# STM32F407VGT6.net
KiCad netlist of a schematic drawn in Altium Designer
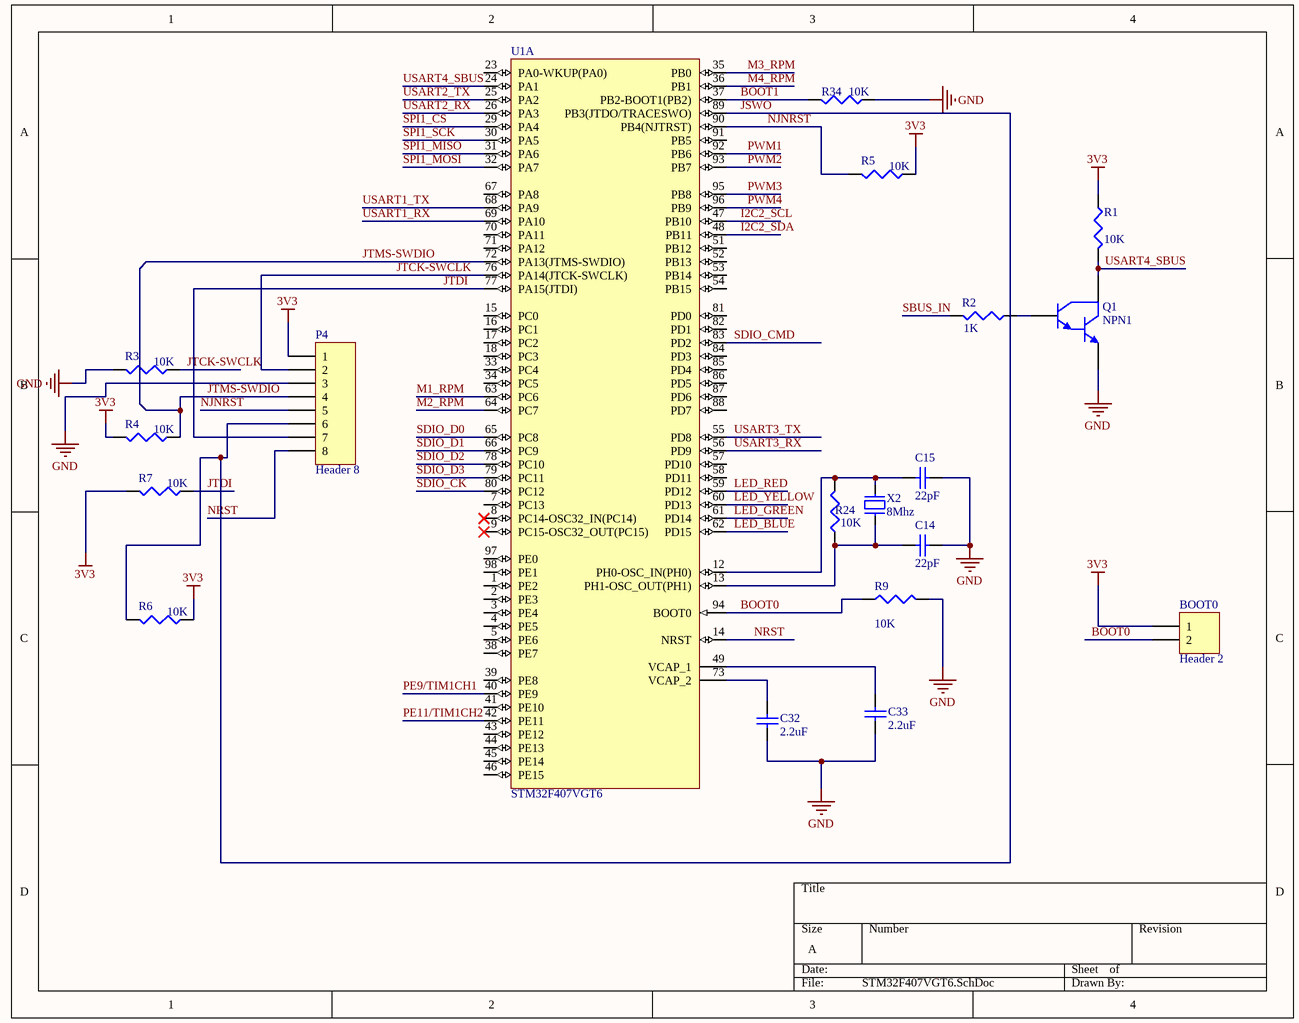
[diagram p0: STM32F407VGT6.SchDoc]

(export (version "E")
  (design (tool "Eeschema 10.0.6"))
  (components
    (comp (ref "BOOT0")
      (value "Header 2")
      (footprint "HDR1X2")
      (description "Header, 2-Pin")
      (fields (field (name "PUBLISHER") "Altium Limited"))
      (libsource (lib "Miscellaneous Connectors") (part "Header 2"))
    )
    (comp (ref "C14")
      (value "22pF")
      (footprint "stm_copter:CAPC1608X95N")
      (description "Capacitor (Semiconductor SIM Model)")
      (fields (field (name "PUBLISHER") "Altium Limited"))
      (libsource (lib "syhaunguyen") (part "Cap Semi"))
    )
    (comp (ref "C15")
      (value "22pF")
      (footprint "stm_copter:CAPC1608X95N")
      (description "Capacitor (Semiconductor SIM Model)")
      (fields (field (name "PUBLISHER") "Altium Limited"))
      (libsource (lib "syhaunguyen") (part "Cap Semi"))
    )
    (comp (ref "C32")
      (value "2.2uF")
      (footprint "stm_copter:CAPC3216X125N")
      (description "Capacitor (Semiconductor SIM Model)")
      (fields (field (name "PUBLISHER") "Altium Limited"))
      (libsource (lib "syhaunguyen") (part "Cap Semi"))
    )
    (comp (ref "C33")
      (value "2.2uF")
      (footprint "stm_copter:CAPC3216X125N")
      (description "Capacitor (Semiconductor SIM Model)")
      (fields (field (name "PUBLISHER") "Altium Limited"))
      (libsource (lib "syhaunguyen") (part "Cap Semi"))
    )
    (comp (ref "P4")
      (value "Header 8")
      (footprint "HDR1X8")
      (description "Header, 8-Pin")
      (fields (field (name "PUBLISHER") "Altium Limited"))
      (libsource (lib "Miscellaneous Connectors") (part "Header 8"))
    )
    (comp (ref "Q1")
      (value "NPN1")
      (footprint "TO-92")
      (description "NPN Darlington Bipolar Transistor")
      (fields (field (name "PUBLISHER") "Altium Limited"))
      (libsource (lib "Miscellaneous Devices") (part "NPN1"))
    )
    (comp (ref "R1")
      (value "10K")
      (footprint "stm_copter:RESC2012X60N")
      (description "Resistor")
      (fields (field (name "PUBLISHER") "Altium Limited"))
      (libsource (lib "Miscellaneous Devices") (part "Res3"))
    )
    (comp (ref "R2")
      (value "1K")
      (footprint "stm_copter:RESC2012X60N")
      (description "Resistor")
      (fields (field (name "PUBLISHER") "Altium Limited"))
      (libsource (lib "Miscellaneous Devices") (part "Res3"))
    )
    (comp (ref "R3")
      (value "10K")
      (footprint "stm_copter:RESC2012X60N")
      (description "Resistor")
      (fields (field (name "PUBLISHER") "Altium Limited"))
      (libsource (lib "Miscellaneous Devices") (part "Res3"))
    )
    (comp (ref "R4")
      (value "10K")
      (footprint "stm_copter:RESC2012X60N")
      (description "Resistor")
      (fields (field (name "PUBLISHER") "Altium Limited"))
      (libsource (lib "Miscellaneous Devices") (part "Res3"))
    )
    (comp (ref "R5")
      (value "10K")
      (footprint "stm_copter:RESC2012X60N")
      (description "Resistor")
      (fields (field (name "PUBLISHER") "Altium Limited"))
      (libsource (lib "Miscellaneous Devices") (part "Res3"))
    )
    (comp (ref "R6")
      (value "10K")
      (footprint "stm_copter:RESC2012X60N")
      (description "Resistor")
      (fields (field (name "PUBLISHER") "Altium Limited"))
      (libsource (lib "Miscellaneous Devices") (part "Res3"))
    )
    (comp (ref "R7")
      (value "10K")
      (footprint "stm_copter:RESC2012X60N")
      (description "Resistor")
      (fields (field (name "PUBLISHER") "Altium Limited"))
      (libsource (lib "Miscellaneous Devices") (part "Res3"))
    )
    (comp (ref "R9")
      (value "10K")
      (footprint "stm_copter:RESC2012X60N")
      (description "Resistor")
      (fields (field (name "PUBLISHER") "Altium Limited"))
      (libsource (lib "Miscellaneous Devices") (part "Res3"))
    )
    (comp (ref "R24")
      (value "10K")
      (footprint "stm_copter:RESC2012X60N")
      (description "Resistor")
      (fields (field (name "PUBLISHER") "Altium Limited"))
      (libsource (lib "Miscellaneous Devices") (part "Res3"))
    )
    (comp (ref "R34")
      (value "10K")
      (footprint "stm_copter:RESC2012X60N")
      (description "Resistor")
      (fields (field (name "PUBLISHER") "Altium Limited"))
      (libsource (lib "Miscellaneous Devices") (part "Res3"))
    )
    (comp (ref "U1")
      (value "STM32F407VGT6")
      (footprint "STM-LQFP100_N")
      (fields (field (name "MANUFACTURER") "STMicroelectronics"))
      (libsource (lib "STMicroelectronics STM32 F4") (part "STM32F407VGT6"))
    )
    (comp (ref "X2")
      (value "8Mhz")
      (footprint "XT2")
      (description "Crystal For all Crystal 2pin.")
      (libsource (lib "syhaunguyen") (part "XT2"))
    )
  )
  (nets
    (net (code "1") (name "/BOOT0") (class "Default")
      (node (ref "BOOT0") (pin "2") (pinfunction "2_2") (pintype "passive"))
      (node (ref "R9") (pin "1") (pinfunction "1_1") (pintype "passive"))
      (node (ref "U1") (pin "94") (pinfunction "BOOT0_94") (pintype "input"))
    )
    (net (code "2") (name "/BOOT1") (class "Default")
      (node (ref "R34") (pin "2") (pinfunction "2_2") (pintype "passive"))
      (node (ref "U1") (pin "37") (pinfunction "PB2-BOOT1(PB2)_37") (pintype "bidirectional"))
    )
    (net (code "3") (name "/I2C2_SCL") (class "Default")
      (node (ref "U1") (pin "47") (pinfunction "PB10_47") (pintype "bidirectional"))
    )
    (net (code "4") (name "/I2C2_SDA") (class "Default")
      (node (ref "U1") (pin "48") (pinfunction "PB11_48") (pintype "bidirectional"))
    )
    (net (code "5") (name "/JSWO") (class "Default")
      (node (ref "P4") (pin "6") (pinfunction "6_6") (pintype "passive"))
      (node (ref "R6") (pin "2") (pinfunction "2_2") (pintype "passive"))
      (node (ref "U1") (pin "89") (pinfunction "PB3(JTDO/TRACESWO)_89") (pintype "bidirectional"))
    )
    (net (code "6") (name "/JTCK-SWCLK") (class "Default")
      (node (ref "P4") (pin "2") (pinfunction "2_2") (pintype "passive"))
      (node (ref "R3") (pin "1") (pinfunction "1_1") (pintype "passive"))
      (node (ref "U1") (pin "76") (pinfunction "PA14(JTCK-SWCLK)_76") (pintype "bidirectional"))
    )
    (net (code "7") (name "/JTDI") (class "Default")
      (node (ref "P4") (pin "7") (pinfunction "7_7") (pintype "passive"))
      (node (ref "R7") (pin "1") (pinfunction "1_1") (pintype "passive"))
      (node (ref "U1") (pin "77") (pinfunction "PA15(JTDI)_77") (pintype "bidirectional"))
    )
    (net (code "8") (name "/JTMS-SWDIO") (class "Default")
      (node (ref "P4") (pin "4") (pinfunction "4_4") (pintype "passive"))
      (node (ref "R4") (pin "1") (pinfunction "1_1") (pintype "passive"))
      (node (ref "U1") (pin "72") (pinfunction "PA13(JTMS-SWDIO)_72") (pintype "bidirectional"))
    )
    (net (code "9") (name "/LED_BLUE") (class "Default")
      (node (ref "U1") (pin "62") (pinfunction "PD15_62") (pintype "bidirectional"))
    )
    (net (code "10") (name "/LED_GREEN") (class "Default")
      (node (ref "U1") (pin "61") (pinfunction "PD14_61") (pintype "bidirectional"))
    )
    (net (code "11") (name "/LED_RED") (class "Default")
      (node (ref "U1") (pin "59") (pinfunction "PD12_59") (pintype "bidirectional"))
    )
    (net (code "12") (name "/LED_YELLOW") (class "Default")
      (node (ref "U1") (pin "60") (pinfunction "PD13_60") (pintype "bidirectional"))
    )
    (net (code "13") (name "/M1_RPM") (class "Default")
      (node (ref "U1") (pin "63") (pinfunction "PC6_63") (pintype "bidirectional"))
    )
    (net (code "14") (name "/M2_RPM") (class "Default")
      (node (ref "U1") (pin "64") (pinfunction "PC7_64") (pintype "bidirectional"))
    )
    (net (code "15") (name "/M3_RPM") (class "Default")
      (node (ref "U1") (pin "35") (pinfunction "PB0_35") (pintype "bidirectional"))
    )
    (net (code "16") (name "/M4_RPM") (class "Default")
      (node (ref "U1") (pin "36") (pinfunction "PB1_36") (pintype "bidirectional"))
    )
    (net (code "17") (name "/NJNRST") (class "Default")
      (node (ref "P4") (pin "5") (pinfunction "5_5") (pintype "passive"))
      (node (ref "R5") (pin "2") (pinfunction "2_2") (pintype "passive"))
      (node (ref "U1") (pin "90") (pinfunction "PB4(NJTRST)_90") (pintype "bidirectional"))
    )
    (net (code "18") (name "/NRST") (class "Default")
      (node (ref "P4") (pin "8") (pinfunction "8_8") (pintype "passive"))
      (node (ref "U1") (pin "14") (pinfunction "NRST_14") (pintype "bidirectional"))
    )
    (net (code "19") (name "/PE9{slash}TIM1CH1") (class "Default")
      (node (ref "U1") (pin "40") (pinfunction "PE9_40") (pintype "bidirectional"))
    )
    (net (code "20") (name "/PE11{slash}TIM1CH2") (class "Default")
      (node (ref "U1") (pin "42") (pinfunction "PE11_42") (pintype "bidirectional"))
    )
    (net (code "21") (name "/PWM1") (class "Default")
      (node (ref "U1") (pin "92") (pinfunction "PB6_92") (pintype "bidirectional"))
    )
    (net (code "22") (name "/PWM2") (class "Default")
      (node (ref "U1") (pin "93") (pinfunction "PB7_93") (pintype "bidirectional"))
    )
    (net (code "23") (name "/PWM3") (class "Default")
      (node (ref "U1") (pin "95") (pinfunction "PB8_95") (pintype "bidirectional"))
    )
    (net (code "24") (name "/PWM4") (class "Default")
      (node (ref "U1") (pin "96") (pinfunction "PB9_96") (pintype "bidirectional"))
    )
    (net (code "25") (name "/SBUS_IN") (class "Default")
      (node (ref "R2") (pin "2") (pinfunction "2_2") (pintype "passive"))
    )
    (net (code "26") (name "/SDIO_CK") (class "Default")
      (node (ref "U1") (pin "80") (pinfunction "PC12_80") (pintype "bidirectional"))
    )
    (net (code "27") (name "/SDIO_CMD") (class "Default")
      (node (ref "U1") (pin "83") (pinfunction "PD2_83") (pintype "bidirectional"))
    )
    (net (code "28") (name "/SDIO_D0") (class "Default")
      (node (ref "U1") (pin "65") (pinfunction "PC8_65") (pintype "bidirectional"))
    )
    (net (code "29") (name "/SDIO_D1") (class "Default")
      (node (ref "U1") (pin "66") (pinfunction "PC9_66") (pintype "bidirectional"))
    )
    (net (code "30") (name "/SDIO_D2") (class "Default")
      (node (ref "U1") (pin "78") (pinfunction "PC10_78") (pintype "bidirectional"))
    )
    (net (code "31") (name "/SDIO_D3") (class "Default")
      (node (ref "U1") (pin "79") (pinfunction "PC11_79") (pintype "bidirectional"))
    )
    (net (code "32") (name "/SPI1_CS") (class "Default")
      (node (ref "U1") (pin "29") (pinfunction "PA4_29") (pintype "bidirectional"))
    )
    (net (code "33") (name "/SPI1_MISO") (class "Default")
      (node (ref "U1") (pin "31") (pinfunction "PA6_31") (pintype "bidirectional"))
    )
    (net (code "34") (name "/SPI1_MOSI") (class "Default")
      (node (ref "U1") (pin "32") (pinfunction "PA7_32") (pintype "bidirectional"))
    )
    (net (code "35") (name "/SPI1_SCK") (class "Default")
      (node (ref "U1") (pin "30") (pinfunction "PA5_30") (pintype "bidirectional"))
    )
    (net (code "36") (name "/USART1_RX") (class "Default")
      (node (ref "U1") (pin "69") (pinfunction "PA10_69") (pintype "bidirectional"))
    )
    (net (code "37") (name "/USART1_TX") (class "Default")
      (node (ref "U1") (pin "68") (pinfunction "PA9_68") (pintype "bidirectional"))
    )
    (net (code "38") (name "/USART2_RX") (class "Default")
      (node (ref "U1") (pin "26") (pinfunction "PA3_26") (pintype "bidirectional"))
    )
    (net (code "39") (name "/USART2_TX") (class "Default")
      (node (ref "U1") (pin "25") (pinfunction "PA2_25") (pintype "bidirectional"))
    )
    (net (code "40") (name "/USART3_RX") (class "Default")
      (node (ref "U1") (pin "56") (pinfunction "PD9_56") (pintype "bidirectional"))
    )
    (net (code "41") (name "/USART3_TX") (class "Default")
      (node (ref "U1") (pin "55") (pinfunction "PD8_55") (pintype "bidirectional"))
    )
    (net (code "42") (name "/USART4_SBUS") (class "Default")
      (node (ref "Q1") (pin "1") (pinfunction "C_1") (pintype "passive"))
      (node (ref "R1") (pin "2") (pinfunction "2_2") (pintype "passive"))
      (node (ref "U1") (pin "24") (pinfunction "PA1_24") (pintype "bidirectional"))
    )
    (net (code "43") (name "3V3") (class "Default")
      (node (ref "BOOT0") (pin "1") (pinfunction "1_1") (pintype "passive"))
      (node (ref "P4") (pin "1") (pinfunction "1_1") (pintype "passive"))
      (node (ref "R1") (pin "1") (pinfunction "1_1") (pintype "passive"))
      (node (ref "R4") (pin "2") (pinfunction "2_2") (pintype "passive"))
      (node (ref "R5") (pin "1") (pinfunction "1_1") (pintype "passive"))
      (node (ref "R6") (pin "1") (pinfunction "1_1") (pintype "passive"))
      (node (ref "R7") (pin "2") (pinfunction "2_2") (pintype "passive"))
    )
    (net (code "44") (name "GND") (class "Default")
      (node (ref "C14") (pin "2") (pinfunction "2_2") (pintype "passive"))
      (node (ref "C15") (pin "2") (pinfunction "2_2") (pintype "passive"))
      (node (ref "C32") (pin "1") (pinfunction "1_1") (pintype "passive"))
      (node (ref "C33") (pin "1") (pinfunction "1_1") (pintype "passive"))
      (node (ref "P4") (pin "3") (pinfunction "3_3") (pintype "passive"))
      (node (ref "Q1") (pin "3") (pinfunction "E_3") (pintype "passive"))
      (node (ref "R3") (pin "2") (pinfunction "2_2") (pintype "passive"))
      (node (ref "R34") (pin "1") (pinfunction "1_1") (pintype "passive"))
      (node (ref "R9") (pin "2") (pinfunction "2_2") (pintype "passive"))
    )
    (net (code "45") (name "Net-(Q1-B)") (class "Default")
      (node (ref "Q1") (pin "2") (pinfunction "B_2") (pintype "passive"))
      (node (ref "R2") (pin "1") (pinfunction "1_1") (pintype "passive"))
    )
    (net (code "46") (name "Net-(U1A-PH0-OSC_IN(PH0))") (class "Default")
      (node (ref "C15") (pin "1") (pinfunction "1_1") (pintype "passive"))
      (node (ref "R24") (pin "2") (pinfunction "2_2") (pintype "passive"))
      (node (ref "U1") (pin "12") (pinfunction "PH0-OSC_IN(PH0)_12") (pintype "bidirectional"))
      (node (ref "X2") (pin "1") (pinfunction "1_1") (pintype "passive"))
    )
    (net (code "47") (name "Net-(U1A-PH1-OSC_OUT(PH1))") (class "Default")
      (node (ref "C14") (pin "1") (pinfunction "1_1") (pintype "passive"))
      (node (ref "R24") (pin "1") (pinfunction "1_1") (pintype "passive"))
      (node (ref "U1") (pin "13") (pinfunction "PH1-OSC_OUT(PH1)_13") (pintype "bidirectional"))
      (node (ref "X2") (pin "2") (pinfunction "2_2") (pintype "passive"))
    )
    (net (code "48") (name "Net-(U1A-VCAP_1)") (class "Default")
      (node (ref "C33") (pin "2") (pinfunction "2_2") (pintype "passive"))
      (node (ref "U1") (pin "49") (pinfunction "VCAP_1_49") (pintype "power_in"))
    )
    (net (code "49") (name "Net-(U1A-VCAP_2)") (class "Default")
      (node (ref "C32") (pin "2") (pinfunction "2_2") (pintype "passive"))
      (node (ref "U1") (pin "73") (pinfunction "VCAP_2_73") (pintype "power_in"))
    )
    (net (code "50") (name "unconnected-(U1A-PA0-WKUP(PA0)-Pad23)") (class "Default")
      (node (ref "U1") (pin "23") (pinfunction "PA0-WKUP(PA0)_23") (pintype "bidirectional"))
    )
    (net (code "51") (name "unconnected-(U1A-PA8-Pad67)") (class "Default")
      (node (ref "U1") (pin "67") (pinfunction "PA8_67") (pintype "bidirectional"))
    )
    (net (code "52") (name "unconnected-(U1A-PA11-Pad70)") (class "Default")
      (node (ref "U1") (pin "70") (pinfunction "PA11_70") (pintype "bidirectional"))
    )
    (net (code "53") (name "unconnected-(U1A-PA12-Pad71)") (class "Default")
      (node (ref "U1") (pin "71") (pinfunction "PA12_71") (pintype "bidirectional"))
    )
    (net (code "54") (name "unconnected-(U1A-PB5-Pad91)") (class "Default")
      (node (ref "U1") (pin "91") (pinfunction "PB5_91") (pintype "bidirectional"))
    )
    (net (code "55") (name "unconnected-(U1A-PB12-Pad51)") (class "Default")
      (node (ref "U1") (pin "51") (pinfunction "PB12_51") (pintype "bidirectional"))
    )
    (net (code "56") (name "unconnected-(U1A-PB13-Pad52)") (class "Default")
      (node (ref "U1") (pin "52") (pinfunction "PB13_52") (pintype "bidirectional"))
    )
    (net (code "57") (name "unconnected-(U1A-PB14-Pad53)") (class "Default")
      (node (ref "U1") (pin "53") (pinfunction "PB14_53") (pintype "bidirectional"))
    )
    (net (code "58") (name "unconnected-(U1A-PB15-Pad54)") (class "Default")
      (node (ref "U1") (pin "54") (pinfunction "PB15_54") (pintype "bidirectional"))
    )
    (net (code "59") (name "unconnected-(U1A-PC0-Pad15)") (class "Default")
      (node (ref "U1") (pin "15") (pinfunction "PC0_15") (pintype "bidirectional"))
    )
    (net (code "60") (name "unconnected-(U1A-PC1-Pad16)") (class "Default")
      (node (ref "U1") (pin "16") (pinfunction "PC1_16") (pintype "bidirectional"))
    )
    (net (code "61") (name "unconnected-(U1A-PC2-Pad17)") (class "Default")
      (node (ref "U1") (pin "17") (pinfunction "PC2_17") (pintype "bidirectional"))
    )
    (net (code "62") (name "unconnected-(U1A-PC3-Pad18)") (class "Default")
      (node (ref "U1") (pin "18") (pinfunction "PC3_18") (pintype "bidirectional"))
    )
    (net (code "63") (name "unconnected-(U1A-PC4-Pad33)") (class "Default")
      (node (ref "U1") (pin "33") (pinfunction "PC4_33") (pintype "bidirectional"))
    )
    (net (code "64") (name "unconnected-(U1A-PC5-Pad34)") (class "Default")
      (node (ref "U1") (pin "34") (pinfunction "PC5_34") (pintype "bidirectional"))
    )
    (net (code "65") (name "unconnected-(U1A-PC13-Pad7)") (class "Default")
      (node (ref "U1") (pin "7") (pinfunction "PC13_7") (pintype "bidirectional"))
    )
    (net (code "66") (name "unconnected-(U1A-PC14-OSC32_IN(PC14)-Pad8)") (class "Default")
      (node (ref "U1") (pin "8") (pinfunction "PC14-OSC32_IN(PC14)_8") (pintype "bidirectional+no_connect"))
    )
    (net (code "67") (name "unconnected-(U1A-PC15-OSC32_OUT(PC15)-Pad9)") (class "Default")
      (node (ref "U1") (pin "9") (pinfunction "PC15-OSC32_OUT(PC15)_9") (pintype "bidirectional+no_connect"))
    )
    (net (code "68") (name "unconnected-(U1A-PD0-Pad81)") (class "Default")
      (node (ref "U1") (pin "81") (pinfunction "PD0_81") (pintype "bidirectional"))
    )
    (net (code "69") (name "unconnected-(U1A-PD1-Pad82)") (class "Default")
      (node (ref "U1") (pin "82") (pinfunction "PD1_82") (pintype "bidirectional"))
    )
    (net (code "70") (name "unconnected-(U1A-PD3-Pad84)") (class "Default")
      (node (ref "U1") (pin "84") (pinfunction "PD3_84") (pintype "bidirectional"))
    )
    (net (code "71") (name "unconnected-(U1A-PD4-Pad85)") (class "Default")
      (node (ref "U1") (pin "85") (pinfunction "PD4_85") (pintype "bidirectional"))
    )
    (net (code "72") (name "unconnected-(U1A-PD5-Pad86)") (class "Default")
      (node (ref "U1") (pin "86") (pinfunction "PD5_86") (pintype "bidirectional"))
    )
    (net (code "73") (name "unconnected-(U1A-PD6-Pad87)") (class "Default")
      (node (ref "U1") (pin "87") (pinfunction "PD6_87") (pintype "bidirectional"))
    )
    (net (code "74") (name "unconnected-(U1A-PD7-Pad88)") (class "Default")
      (node (ref "U1") (pin "88") (pinfunction "PD7_88") (pintype "bidirectional"))
    )
    (net (code "75") (name "unconnected-(U1A-PD10-Pad57)") (class "Default")
      (node (ref "U1") (pin "57") (pinfunction "PD10_57") (pintype "bidirectional"))
    )
    (net (code "76") (name "unconnected-(U1A-PD11-Pad58)") (class "Default")
      (node (ref "U1") (pin "58") (pinfunction "PD11_58") (pintype "bidirectional"))
    )
    (net (code "77") (name "unconnected-(U1A-PE0-Pad97)") (class "Default")
      (node (ref "U1") (pin "97") (pinfunction "PE0_97") (pintype "bidirectional"))
    )
    (net (code "78") (name "unconnected-(U1A-PE1-Pad98)") (class "Default")
      (node (ref "U1") (pin "98") (pinfunction "PE1_98") (pintype "bidirectional"))
    )
    (net (code "79") (name "unconnected-(U1A-PE2-Pad1)") (class "Default")
      (node (ref "U1") (pin "1") (pinfunction "PE2_1") (pintype "bidirectional"))
    )
    (net (code "80") (name "unconnected-(U1A-PE3-Pad2)") (class "Default")
      (node (ref "U1") (pin "2") (pinfunction "PE3_2") (pintype "bidirectional"))
    )
    (net (code "81") (name "unconnected-(U1A-PE4-Pad3)") (class "Default")
      (node (ref "U1") (pin "3") (pinfunction "PE4_3") (pintype "bidirectional"))
    )
    (net (code "82") (name "unconnected-(U1A-PE5-Pad4)") (class "Default")
      (node (ref "U1") (pin "4") (pinfunction "PE5_4") (pintype "bidirectional"))
    )
    (net (code "83") (name "unconnected-(U1A-PE6-Pad5)") (class "Default")
      (node (ref "U1") (pin "5") (pinfunction "PE6_5") (pintype "bidirectional"))
    )
    (net (code "84") (name "unconnected-(U1A-PE7-Pad38)") (class "Default")
      (node (ref "U1") (pin "38") (pinfunction "PE7_38") (pintype "bidirectional"))
    )
    (net (code "85") (name "unconnected-(U1A-PE8-Pad39)") (class "Default")
      (node (ref "U1") (pin "39") (pinfunction "PE8_39") (pintype "bidirectional"))
    )
    (net (code "86") (name "unconnected-(U1A-PE10-Pad41)") (class "Default")
      (node (ref "U1") (pin "41") (pinfunction "PE10_41") (pintype "bidirectional"))
    )
    (net (code "87") (name "unconnected-(U1A-PE12-Pad43)") (class "Default")
      (node (ref "U1") (pin "43") (pinfunction "PE12_43") (pintype "bidirectional"))
    )
    (net (code "88") (name "unconnected-(U1A-PE13-Pad44)") (class "Default")
      (node (ref "U1") (pin "44") (pinfunction "PE13_44") (pintype "bidirectional"))
    )
    (net (code "89") (name "unconnected-(U1A-PE14-Pad45)") (class "Default")
      (node (ref "U1") (pin "45") (pinfunction "PE14_45") (pintype "bidirectional"))
    )
    (net (code "90") (name "unconnected-(U1A-PE15-Pad46)") (class "Default")
      (node (ref "U1") (pin "46") (pinfunction "PE15_46") (pintype "bidirectional"))
    )
  )
)
